# DB10012_ControlUSBSerial.net
KiCad netlist of a schematic drawn in Altium Designer
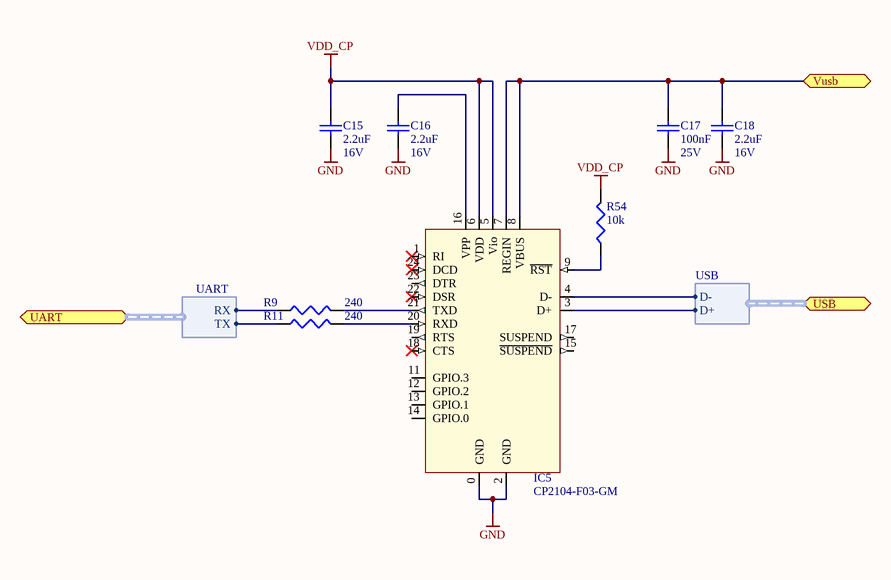
[diagram p0: DB10012_ControlUSBSerial.SchDoc]

(export (version "E")
  (design (tool "Eeschema 10.0.6"))
  (components
    (comp (ref "C15")
      (value "2.2uF")
      (footprint "C0603")
      (description "Capacitor, 2.2uF, 16V, X5R")
      (fields (field (name "VOLTAGE RATING") "16V"))
      (libsource (lib "AR_Capacitors_Ceramic") (part "2.2uF/0603/CER/16V"))
    )
    (comp (ref "C16")
      (value "2.2uF")
      (footprint "C0603")
      (description "Capacitor, 2.2uF, 16V, X5R")
      (fields (field (name "VOLTAGE RATING") "16V"))
      (libsource (lib "AR_Capacitors_Ceramic") (part "2.2uF/0603/CER/16V"))
    )
    (comp (ref "C17")
      (value "100nF")
      (footprint "C0402")
      (description "Capacitor, 100nF, 25V, X7R")
      (fields (field (name "VOLTAGE RATING") "25V"))
      (libsource (lib "AR_Capacitors_Ceramic") (part "100nF/0402/CER/25V"))
    )
    (comp (ref "C18")
      (value "2.2uF")
      (footprint "C0603")
      (description "Capacitor, 2.2uF, 16V, X5R")
      (fields (field (name "VOLTAGE RATING") "16V"))
      (libsource (lib "AR_Capacitors_Ceramic") (part "2.2uF/0603/CER/16V"))
    )
    (comp (ref "IC5")
      (value "CP2104-F03-GM")
      (footprint "QFN24")
      (description "USB to UART converter")
      (libsource (lib "AR_ICs") (part "CP2104-F03-GM"))
    )
    (comp (ref "R9")
      (value "240")
      (footprint "0402")
      (description "Resistor, 240, 0.1%, 0.0625W, 50V, 100PPM, 0402")
      (libsource (lib "AR_Resistors_SMD") (part "240/0402/0063W/50V"))
    )
    (comp (ref "R11")
      (value "240")
      (footprint "0402")
      (description "Resistor, 240, 0.1%, 0.0625W, 50V, 100PPM, 0402")
      (libsource (lib "AR_Resistors_SMD") (part "240/0402/0063W/50V"))
    )
    (comp (ref "R54")
      (value "10k")
      (footprint "0402")
      (description "Resistor, 10k, 0.1%, 0.0625W, 50V, 100PPM, 0402")
      (libsource (lib "AR_Resistors_SMD") (part "10k/0402/0063W/50V"))
    )
  )
  (nets
    (net (code "3") (name "/D+") (class "Default")
      (node (ref "IC5") (pin "3") (pinfunction "D+_3") (pintype "bidirectional"))
    )
    (net (code "4") (name "/D-") (class "Default")
      (node (ref "IC5") (pin "4") (pinfunction "D-_4") (pintype "bidirectional"))
    )
    (net (code "5") (name "/RX") (class "Default")
      (node (ref "R9") (pin "1") (pinfunction "1_1") (pintype "passive"))
    )
    (net (code "6") (name "/TX") (class "Default")
      (node (ref "R11") (pin "1") (pinfunction "1_1") (pintype "passive"))
    )
    (net (code "7") (name "/Vusb") (class "Default")
      (node (ref "C17") (pin "2") (pinfunction "2_2") (pintype "passive"))
      (node (ref "C18") (pin "2") (pinfunction "2_2") (pintype "passive"))
      (node (ref "IC5") (pin "7") (pinfunction "REGIN_7") (pintype "power_in"))
      (node (ref "IC5") (pin "8") (pinfunction "VBUS_8") (pintype "power_in"))
    )
    (net (code "10") (name "GND") (class "Default")
      (node (ref "C15") (pin "1") (pinfunction "1_1") (pintype "passive"))
      (node (ref "C16") (pin "1") (pinfunction "1_1") (pintype "passive"))
      (node (ref "C17") (pin "1") (pinfunction "1_1") (pintype "passive"))
      (node (ref "C18") (pin "1") (pinfunction "1_1") (pintype "passive"))
      (node (ref "IC5") (pin "0") (pinfunction "GND_0") (pintype "power_in"))
      (node (ref "IC5") (pin "2") (pinfunction "GND_2") (pintype "power_in"))
    )
    (net (code "11") (name "Net-(IC5-RXD)") (class "Default")
      (node (ref "IC5") (pin "20") (pinfunction "RXD_20") (pintype "input"))
      (node (ref "R11") (pin "2") (pinfunction "2_2") (pintype "passive"))
    )
    (net (code "12") (name "Net-(IC5-TXD)") (class "Default")
      (node (ref "IC5") (pin "21") (pinfunction "TXD_21") (pintype "output"))
      (node (ref "R9") (pin "2") (pinfunction "2_2") (pintype "passive"))
    )
    (net (code "13") (name "Net-(IC5-VPP)") (class "Default")
      (node (ref "C16") (pin "2") (pinfunction "2_2") (pintype "passive"))
      (node (ref "IC5") (pin "16") (pinfunction "VPP_16") (pintype "power_in"))
    )
    (net (code "14") (name "Net-(IC5-~{RST})") (class "Default")
      (node (ref "IC5") (pin "9") (pinfunction "~{RST}_9") (pintype "input"))
      (node (ref "R54") (pin "1") (pinfunction "1_1") (pintype "passive"))
    )
    (net (code "15") (name "VDD_CP") (class "Default")
      (node (ref "C15") (pin "2") (pinfunction "2_2") (pintype "passive"))
      (node (ref "IC5") (pin "5") (pinfunction "Vio_5") (pintype "passive"))
      (node (ref "IC5") (pin "6") (pinfunction "VDD_6") (pintype "power_in"))
      (node (ref "R54") (pin "2") (pinfunction "2_2") (pintype "passive"))
    )
    (net (code "16") (name "unconnected-(IC5-CTS-Pad18)") (class "Default")
      (node (ref "IC5") (pin "18") (pinfunction "CTS_18") (pintype "input+no_connect"))
    )
    (net (code "17") (name "unconnected-(IC5-DCD-Pad24)") (class "Default")
      (node (ref "IC5") (pin "24") (pinfunction "DCD_24") (pintype "input+no_connect"))
    )
    (net (code "18") (name "unconnected-(IC5-DSR-Pad22)") (class "Default")
      (node (ref "IC5") (pin "22") (pinfunction "DSR_22") (pintype "input+no_connect"))
    )
    (net (code "19") (name "unconnected-(IC5-DTR-Pad23)") (class "Default")
      (node (ref "IC5") (pin "23") (pinfunction "DTR_23") (pintype "output"))
    )
    (net (code "20") (name "unconnected-(IC5-GPIO.0-Pad14)") (class "Default")
      (node (ref "IC5") (pin "14") (pinfunction "GPIO.0_14") (pintype "passive"))
    )
    (net (code "21") (name "unconnected-(IC5-GPIO.1-Pad13)") (class "Default")
      (node (ref "IC5") (pin "13") (pinfunction "GPIO.1_13") (pintype "passive"))
    )
    (net (code "22") (name "unconnected-(IC5-GPIO.2-Pad12)") (class "Default")
      (node (ref "IC5") (pin "12") (pinfunction "GPIO.2_12") (pintype "passive"))
    )
    (net (code "23") (name "unconnected-(IC5-GPIO.3-Pad11)") (class "Default")
      (node (ref "IC5") (pin "11") (pinfunction "GPIO.3_11") (pintype "passive"))
    )
    (net (code "24") (name "unconnected-(IC5-RI-Pad1)") (class "Default")
      (node (ref "IC5") (pin "1") (pinfunction "RI_1") (pintype "input+no_connect"))
    )
    (net (code "25") (name "unconnected-(IC5-RTS-Pad19)") (class "Default")
      (node (ref "IC5") (pin "19") (pinfunction "RTS_19") (pintype "output"))
    )
    (net (code "26") (name "unconnected-(IC5-SUSPEND-Pad17)") (class "Default")
      (node (ref "IC5") (pin "17") (pinfunction "SUSPEND_17") (pintype "output"))
    )
    (net (code "27") (name "unconnected-(IC5-~{SUSPEND}-Pad15)") (class "Default")
      (node (ref "IC5") (pin "15") (pinfunction "~{SUSPEND}_15") (pintype "output"))
    )
  )
)
